# analog_driver_s.net
KiCad netlist of a schematic drawn in EAGLE
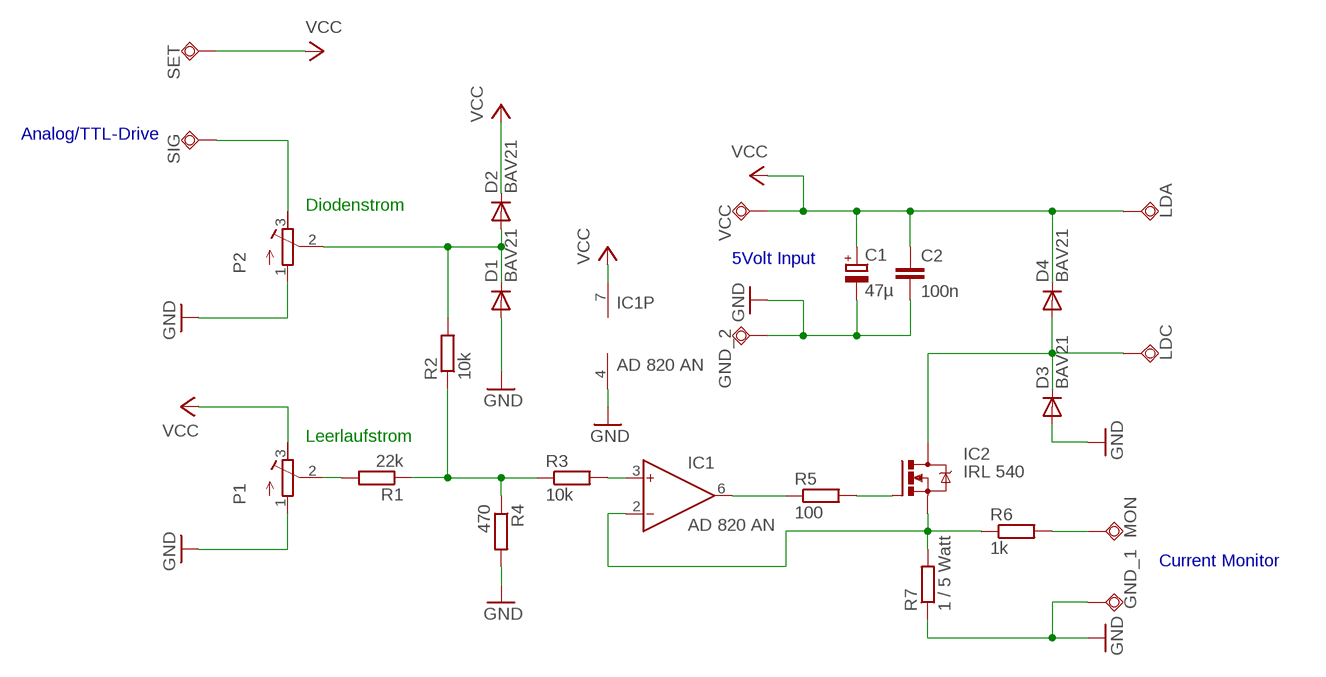
[diagram p0: schematic, sheet 1]

(export (version "E")
  (design (tool "Eeschema 10.0.6"))
  (components
    (comp (ref "C1")
      (value "47µ")
      (footprint "eagle-import:E2-5")
      (libsource (lib "eagle-import") (part "CPOL-EUE2-5"))
    )
    (comp (ref "C2")
      (value "100n")
      (footprint "eagle-import:C025-024X044")
      (libsource (lib "eagle-import") (part "C-EU025-024X044"))
    )
    (comp (ref "D1")
      (value "BAV21")
      (footprint "eagle-import:DO35-10")
      (libsource (lib "eagle-import") (part "BAV21"))
    )
    (comp (ref "D2")
      (value "BAV21")
      (footprint "eagle-import:DO35-10")
      (libsource (lib "eagle-import") (part "BAV21"))
    )
    (comp (ref "D3")
      (value "BAV21")
      (footprint "eagle-import:DO35-10")
      (libsource (lib "eagle-import") (part "BAV21"))
    )
    (comp (ref "D4")
      (value "BAV21")
      (footprint "eagle-import:DO35-10")
      (libsource (lib "eagle-import") (part "BAV21"))
    )
    (comp (ref "GND_1")
      (value "PAD")
      (footprint "eagle-import:PAD")
      (libsource (lib "eagle-import") (part "PAD"))
    )
    (comp (ref "GND_2")
      (value "PAD")
      (footprint "eagle-import:PAD")
      (libsource (lib "eagle-import") (part "PAD"))
    )
    (comp (ref "IC1")
      (value "AD 820 AN")
      (footprint "eagle-import:DIL08")
      (libsource (lib "eagle-import") (part "AD811_N"))
    )
    (comp (ref "IC2")
      (value "IRL 540")
      (footprint "eagle-import:TO220BV")
      (libsource (lib "eagle-import") (part "IRF540"))
    )
    (comp (ref "LDA")
      (value "PAD")
      (footprint "eagle-import:PAD")
      (libsource (lib "eagle-import") (part "PAD"))
    )
    (comp (ref "LDC")
      (value "PAD")
      (footprint "eagle-import:PAD")
      (libsource (lib "eagle-import") (part "PAD"))
    )
    (comp (ref "MON")
      (value "PAD")
      (footprint "eagle-import:PAD")
      (libsource (lib "eagle-import") (part "PAD"))
    )
    (comp (ref "P1")
      (value "R-TRIMM3296W")
      (footprint "eagle-import:RTRIM3296W")
      (libsource (lib "eagle-import") (part "R-TRIMM3296W"))
    )
    (comp (ref "P2")
      (value "R-TRIMM3296W")
      (footprint "eagle-import:RTRIM3296W")
      (libsource (lib "eagle-import") (part "R-TRIMM3296W"))
    )
    (comp (ref "R1")
      (value "22k")
      (footprint "eagle-import:0309V")
      (libsource (lib "eagle-import") (part "R-EU_0309/V"))
    )
    (comp (ref "R2")
      (value "10k")
      (footprint "eagle-import:0309V")
      (libsource (lib "eagle-import") (part "R-EU_0309/V"))
    )
    (comp (ref "R3")
      (value "10k")
      (footprint "eagle-import:0309_10")
      (libsource (lib "eagle-import") (part "R-EU_0309/10"))
    )
    (comp (ref "R4")
      (value "470")
      (footprint "eagle-import:0309V")
      (libsource (lib "eagle-import") (part "R-EU_0309/V"))
    )
    (comp (ref "R5")
      (value "100")
      (footprint "eagle-import:0309V")
      (libsource (lib "eagle-import") (part "R-EU_0309/V"))
    )
    (comp (ref "R6")
      (value "1k")
      (footprint "eagle-import:0309V")
      (libsource (lib "eagle-import") (part "R-EU_0309/V"))
    )
    (comp (ref "R7")
      (value "1 / 5 Watt")
      (footprint "eagle-import:0617V")
      (libsource (lib "eagle-import") (part "R-EU_0617/5V"))
    )
    (comp (ref "SET")
      (value "PAD")
      (footprint "eagle-import:PAD")
      (libsource (lib "eagle-import") (part "PAD"))
    )
    (comp (ref "SIG")
      (value "PAD")
      (footprint "eagle-import:PAD")
      (libsource (lib "eagle-import") (part "PAD"))
    )
    (comp (ref "VCC")
      (value "PAD")
      (footprint "eagle-import:PAD")
      (libsource (lib "eagle-import") (part "PAD"))
    )
  )
  (nets
    (net (code "1") (name "GND") (class "Default")
      (node (ref "C1") (pin "-") (pinfunction "-_-") (pintype "passive"))
      (node (ref "C2") (pin "2") (pinfunction "2_2") (pintype "passive"))
      (node (ref "D1") (pin "A") (pinfunction "A_A") (pintype "passive"))
      (node (ref "D3") (pin "A") (pinfunction "A_A") (pintype "passive"))
      (node (ref "GND_1") (pin "P$1") (pinfunction "TP_P$1") (pintype "input"))
      (node (ref "GND_2") (pin "P$1") (pinfunction "TP_P$1") (pintype "input"))
      (node (ref "IC1") (pin "4") (pinfunction "V-_4") (pintype "power_in"))
      (node (ref "P1") (pin "1") (pinfunction "E_1") (pintype "passive"))
      (node (ref "P2") (pin "1") (pinfunction "E_1") (pintype "passive"))
      (node (ref "R4") (pin "2") (pinfunction "2_2") (pintype "passive"))
      (node (ref "R7") (pin "1") (pinfunction "1_1") (pintype "passive"))
    )
    (net (code "2") (name "Net-(IC1D-IN+)") (class "Default")
      (node (ref "IC1") (pin "3") (pinfunction "IN+_3") (pintype "input"))
      (node (ref "R3") (pin "2") (pinfunction "2_2") (pintype "passive"))
    )
    (net (code "3") (name "Net-(IC1D-IN-)") (class "Default")
      (node (ref "IC1") (pin "2") (pinfunction "IN-_2") (pintype "input"))
      (node (ref "IC2") (pin "S") (pinfunction "S_S") (pintype "passive"))
      (node (ref "R6") (pin "1") (pinfunction "1_1") (pintype "passive"))
      (node (ref "R7") (pin "2") (pinfunction "2_2") (pintype "passive"))
    )
    (net (code "4") (name "Net-(IC1D-OUT)") (class "Default")
      (node (ref "IC1") (pin "6") (pinfunction "OUT_6") (pintype "output"))
      (node (ref "R5") (pin "1") (pinfunction "1_1") (pintype "passive"))
    )
    (net (code "5") (name "Net-(IC2-PadG)") (class "Default")
      (node (ref "IC2") (pin "G") (pinfunction "G_G") (pintype "passive"))
      (node (ref "R5") (pin "2") (pinfunction "2_2") (pintype "passive"))
    )
    (net (code "6") (name "Net-(LDC-TP)") (class "Default")
      (node (ref "D3") (pin "C") (pinfunction "C_C") (pintype "passive"))
      (node (ref "D4") (pin "A") (pinfunction "A_A") (pintype "passive"))
      (node (ref "IC2") (pin "D") (pinfunction "D_D") (pintype "passive"))
      (node (ref "LDC") (pin "P$1") (pinfunction "TP_P$1") (pintype "input"))
    )
    (net (code "7") (name "Net-(MON-TP)") (class "Default")
      (node (ref "MON") (pin "P$1") (pinfunction "TP_P$1") (pintype "input"))
      (node (ref "R6") (pin "2") (pinfunction "2_2") (pintype "passive"))
    )
    (net (code "8") (name "Net-(P1-S)") (class "Default")
      (node (ref "P1") (pin "2") (pinfunction "S_2") (pintype "passive"))
      (node (ref "R1") (pin "2") (pinfunction "2_2") (pintype "passive"))
    )
    (net (code "9") (name "Net-(P2-A)") (class "Default")
      (node (ref "P2") (pin "3") (pinfunction "A_3") (pintype "passive"))
      (node (ref "SIG") (pin "P$1") (pinfunction "TP_P$1") (pintype "input"))
    )
    (net (code "10") (name "Net-(P2-S)") (class "Default")
      (node (ref "D1") (pin "C") (pinfunction "C_C") (pintype "passive"))
      (node (ref "D2") (pin "A") (pinfunction "A_A") (pintype "passive"))
      (node (ref "P2") (pin "2") (pinfunction "S_2") (pintype "passive"))
      (node (ref "R2") (pin "2") (pinfunction "2_2") (pintype "passive"))
    )
    (net (code "11") (name "Net-(R1-Pad1)") (class "Default")
      (node (ref "R1") (pin "1") (pinfunction "1_1") (pintype "passive"))
      (node (ref "R2") (pin "1") (pinfunction "1_1") (pintype "passive"))
      (node (ref "R3") (pin "1") (pinfunction "1_1") (pintype "passive"))
      (node (ref "R4") (pin "1") (pinfunction "1_1") (pintype "passive"))
    )
    (net (code "12") (name "VCC") (class "Default")
      (node (ref "C1") (pin "+") (pinfunction "+_+") (pintype "passive"))
      (node (ref "C2") (pin "1") (pinfunction "1_1") (pintype "passive"))
      (node (ref "D2") (pin "C") (pinfunction "C_C") (pintype "passive"))
      (node (ref "D4") (pin "C") (pinfunction "C_C") (pintype "passive"))
      (node (ref "IC1") (pin "7") (pinfunction "V+_7") (pintype "power_in"))
      (node (ref "LDA") (pin "P$1") (pinfunction "TP_P$1") (pintype "input"))
      (node (ref "P1") (pin "3") (pinfunction "A_3") (pintype "passive"))
      (node (ref "SET") (pin "P$1") (pinfunction "TP_P$1") (pintype "input"))
      (node (ref "VCC") (pin "P$1") (pinfunction "TP_P$1") (pintype "input"))
    )
  )
)
